# ThrusterControl.net
KiCad netlist of a schematic drawn in Altium Designer
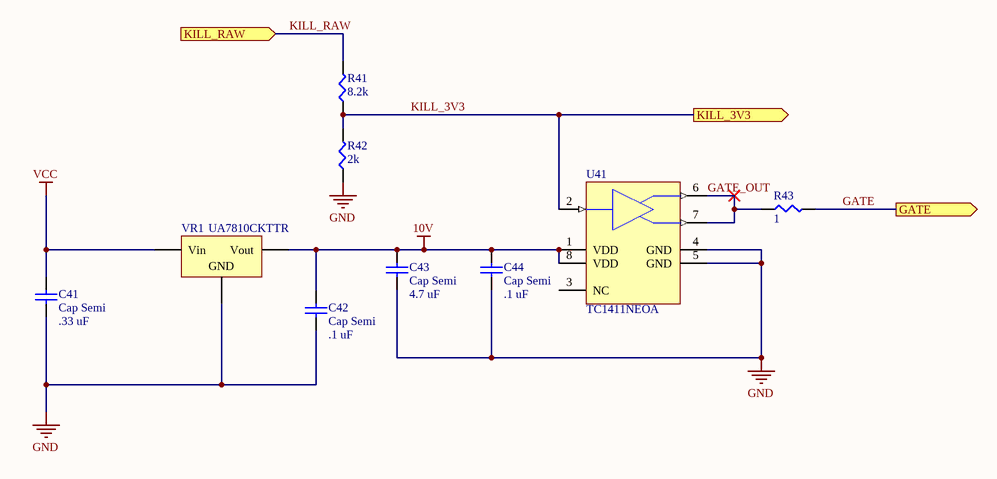
[diagram p0: ThrusterControl.SchDoc]

(export (version "E")
  (design (tool "Eeschema 10.0.6"))
  (components
    (comp (ref "C41")
      (value "Cap Semi")
      (footprint "C1206")
      (description "Capacitor (Semiconductor SIM Model)")
      (fields (field (name "ALTIUM_VALUE") ".33 uF") (field (name "PUBLISHER") "Altium Limited"))
      (libsource (lib "Miscellaneous Devices") (part "Cap Semi"))
    )
    (comp (ref "C42")
      (value "Cap Semi")
      (footprint "C1206")
      (description "Capacitor (Semiconductor SIM Model)")
      (fields (field (name "ALTIUM_VALUE") ".1 uF") (field (name "PUBLISHER") "Altium Limited"))
      (libsource (lib "Miscellaneous Devices") (part "Cap Semi"))
    )
    (comp (ref "C43")
      (value "Cap Semi")
      (footprint "C1206")
      (description "Capacitor (Semiconductor SIM Model)")
      (fields (field (name "ALTIUM_VALUE") "4.7 uF") (field (name "PUBLISHER") "Altium Limited"))
      (libsource (lib "Miscellaneous Devices") (part "Cap Semi"))
    )
    (comp (ref "C44")
      (value "Cap Semi")
      (footprint "C1206")
      (description "Capacitor (Semiconductor SIM Model)")
      (fields (field (name "ALTIUM_VALUE") ".1 uF") (field (name "PUBLISHER") "Altium Limited"))
      (libsource (lib "Miscellaneous Devices") (part "Cap Semi"))
    )
    (comp (ref "R41")
      (value "8.2k")
      (footprint "SMD-1206-RES")
      (description "RES SMD 8.2K OHM 1% 1/4W 1206")
      (fields
        (field (name "PART NUMBER") "ERJ-8ENF8201V")
        (field (name "DIGI-KEY PART NUMBER") "P8.20KFCT-ND")
      )
      (libsource (lib "Panasonic_ERJ_1206") (part "ERJ-8ENF8201V"))
    )
    (comp (ref "R42")
      (value "2k")
      (footprint "SMD-1206-RES")
      (description "RES SMD 2K OHM 5% 2/3W 1206")
      (fields
        (field (name "PART NUMBER") "ERJ-P08J202V")
        (field (name "DIGI-KEY PART NUMBER") "P2.0KALCT-ND")
      )
      (libsource (lib "Panasonic_ERJ_1206") (part "ERJ-P08J202V"))
    )
    (comp (ref "R43")
      (value "1")
      (footprint "SMD-1206-RES")
      (description "RES SMD 1 OHM 1% 1/2W 1206")
      (fields (field (name "PART NUMBER") "ERJ-8BQF1R0V") (field (name "DIGI-KEY PART NUMBER") "P17600CT-ND"))
      (libsource (lib "Panasonic_ERJ_1206") (part "ERJ-8BQF1R0V"))
    )
    (comp (ref "U41")
      (value "TC1411NEOA")
      (footprint "SOIC-OA8_M")
      (description "1A High-Speed MOSFET Driver, Non-Inverting, Industrial Temperature")
      (libsource (lib "Altium Content Vault") (part "IN-MOSDRV-TC1410N-8"))
    )
    (comp (ref "VR1")
      (value "UA7810CKTTR")
      (footprint "D2PAK_L")
      (description "Voltage Regulator")
      (fields (field (name "PUBLISHER") "Altium Limited"))
      (libsource (lib "Miscellaneous Devices") (part "Volt Reg"))
    )
  )
  (nets
    (net (code "1") (name "/GATE") (class "Default")
      (node (ref "R43") (pin "2") (pinfunction "2_2") (pintype "passive"))
    )
    (net (code "2") (name "/GATE_OUT") (class "Default")
      (node (ref "R43") (pin "1") (pinfunction "1_1") (pintype "passive"))
      (node (ref "U41") (pin "6") (pinfunction "OUT_6") (pintype "output"))
      (node (ref "U41") (pin "7") (pinfunction "OUT_7") (pintype "output"))
    )
    (net (code "3") (name "/KILL_3V3") (class "Default")
      (node (ref "R41") (pin "1") (pinfunction "1_1") (pintype "passive"))
      (node (ref "R42") (pin "2") (pinfunction "2_2") (pintype "passive"))
      (node (ref "U41") (pin "2") (pinfunction "IN_2") (pintype "input"))
    )
    (net (code "4") (name "/KILL_RAW") (class "Default")
      (node (ref "R41") (pin "2") (pinfunction "2_2") (pintype "passive"))
    )
    (net (code "5") (name "10V") (class "Default")
      (node (ref "C42") (pin "2") (pinfunction "2_2") (pintype "passive"))
      (node (ref "C43") (pin "2") (pinfunction "2_2") (pintype "passive"))
      (node (ref "C44") (pin "2") (pinfunction "2_2") (pintype "passive"))
      (node (ref "U41") (pin "1") (pinfunction "VDD_1") (pintype "power_in"))
      (node (ref "U41") (pin "8") (pinfunction "VDD_8") (pintype "power_in"))
      (node (ref "VR1") (pin "3") (pinfunction "Vout_3") (pintype "passive"))
    )
    (net (code "6") (name "GND") (class "Default")
      (node (ref "C41") (pin "1") (pinfunction "1_1") (pintype "passive"))
      (node (ref "C42") (pin "1") (pinfunction "1_1") (pintype "passive"))
      (node (ref "C43") (pin "1") (pinfunction "1_1") (pintype "passive"))
      (node (ref "C44") (pin "1") (pinfunction "1_1") (pintype "passive"))
      (node (ref "R42") (pin "1") (pinfunction "1_1") (pintype "passive"))
      (node (ref "U41") (pin "4") (pinfunction "GND_4") (pintype "power_in"))
      (node (ref "U41") (pin "5") (pinfunction "GND_5") (pintype "power_in"))
      (node (ref "VR1") (pin "2") (pinfunction "GND_2") (pintype "passive"))
    )
    (net (code "7") (name "VCC") (class "Default")
      (node (ref "C41") (pin "2") (pinfunction "2_2") (pintype "passive"))
      (node (ref "VR1") (pin "1") (pinfunction "Vin_1") (pintype "passive"))
    )
    (net (code "8") (name "unconnected-(U41-NC-Pad3)") (class "Default")
      (node (ref "U41") (pin "3") (pinfunction "NC_3") (pintype "passive"))
    )
  )
)
